# CAN.net
KiCad netlist of a schematic drawn in Altium Designer
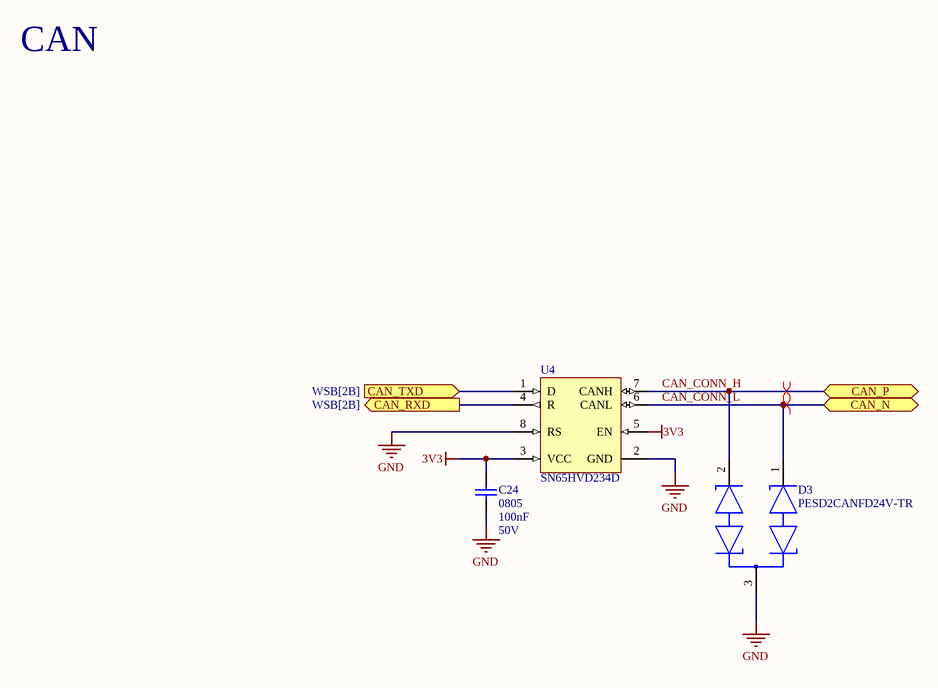
[diagram p0: CAN.SchDoc]

(export (version "E")
  (design (tool "Eeschema 10.0.6"))
  (components
    (comp (ref "C24")
      (value "C0805C104K5RACTU")
      (footprint "CAPC2013X88X50NL20T25")
      (fields
        (field (name "MANUFACTURER") "Kemet")
        (field (name "CASE CODE (IMPERIAL)") "0805")
        (field (name "CAPACITANCE") "100nF")
        (field (name "VOLTAGE RATING") "50V")
        (field (name "TOLERANCE") "10%")
        (field (name "VOLTAGE") "500V")
      )
      (libsource (lib "Altium Content Vault") (part "CAP"))
    )
    (comp (ref "D3")
      (value "PESD2CANFD24V-TR")
      (footprint "FP-SOT23-IPC_A")
      (description "TVS DIODE 24VWM 42VC TO236AB")
      (libsource (lib "Altium Content Vault") (part "e1aa1e71a25486d94450bfc930cdd33"))
    )
    (comp (ref "U4")
      (value "SN65HVD234D")
      (footprint "D0008A_M")
      (fields (field (name "MANUFACTURER") "Texas Instruments"))
      (libsource (lib "Altium Content Vault") (part "TI-SN65HVD234-SOIC_D-8"))
    )
  )
  (nets
    (net (code "1") (name "/CAN_CONN_H") (class "Default")
      (node (ref "D3") (pin "2") (pinfunction "K2_2") (pintype "passive"))
      (node (ref "U4") (pin "7") (pinfunction "CANH_7") (pintype "bidirectional"))
    )
    (net (code "2") (name "/CAN_CONN_L") (class "Default")
      (node (ref "D3") (pin "1") (pinfunction "K1_1") (pintype "passive"))
      (node (ref "U4") (pin "6") (pinfunction "CANL_6") (pintype "bidirectional"))
    )
    (net (code "3") (name "/CAN_RXD") (class "Default")
      (node (ref "U4") (pin "4") (pinfunction "R_4") (pintype "output"))
    )
    (net (code "4") (name "/CAN_TXD") (class "Default")
      (node (ref "U4") (pin "1") (pinfunction "D_1") (pintype "input"))
    )
    (net (code "5") (name "3V3") (class "Default")
      (node (ref "C24") (pin "1") (pinfunction "1_1") (pintype "passive"))
      (node (ref "U4") (pin "3") (pinfunction "VCC_3") (pintype "input"))
      (node (ref "U4") (pin "5") (pinfunction "EN_5") (pintype "input"))
    )
    (net (code "6") (name "GND") (class "Default")
      (node (ref "C24") (pin "2") (pinfunction "2_2") (pintype "passive"))
      (node (ref "D3") (pin "3") (pinfunction "CC_3") (pintype "passive"))
      (node (ref "U4") (pin "2") (pinfunction "GND_2") (pintype "power_in"))
      (node (ref "U4") (pin "8") (pinfunction "RS_8") (pintype "input"))
    )
  )
)
